# STM32F407ZGT6.net
KiCad netlist of a schematic drawn in Altium Designer
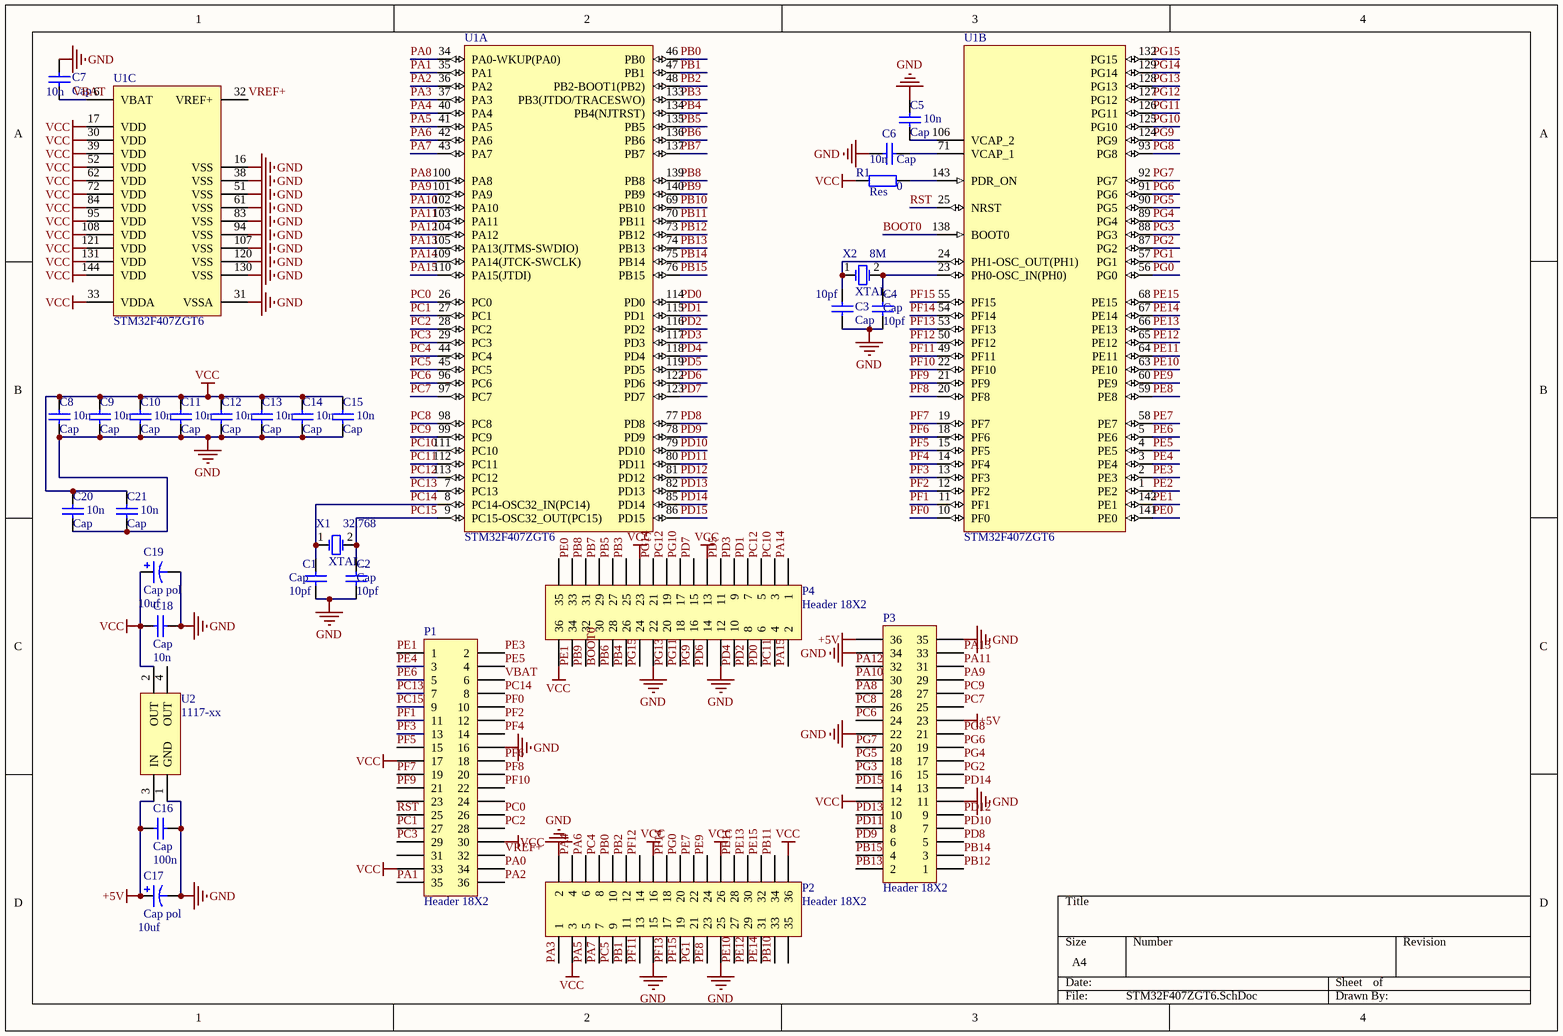
[diagram p0: STM32F407ZGT6.SchDoc]

(export (version "E")
  (design (tool "Eeschema 10.0.6"))
  (components
    (comp (ref "C1")
      (value "Cap")
      (footprint "0805C")
      (description "无极性电容")
      (fields (field (name "ALTIUM_VALUE") "10pf"))
      (libsource (lib "unsal_Devices") (part "Cap"))
    )
    (comp (ref "C2")
      (value "Cap")
      (footprint "0805C")
      (description "无极性电容")
      (fields (field (name "ALTIUM_VALUE") "10pf"))
      (libsource (lib "unsal_Devices") (part "Cap"))
    )
    (comp (ref "C3")
      (value "Cap")
      (footprint "0805C")
      (description "无极性电容")
      (fields (field (name "ALTIUM_VALUE") "10pf"))
      (libsource (lib "unsal_Devices") (part "Cap"))
    )
    (comp (ref "C4")
      (value "Cap")
      (footprint "0805C")
      (description "无极性电容")
      (fields (field (name "ALTIUM_VALUE") "10pf"))
      (libsource (lib "unsal_Devices") (part "Cap"))
    )
    (comp (ref "C5")
      (value "Cap")
      (footprint "0805C")
      (description "无极性电容")
      (fields (field (name "ALTIUM_VALUE") "10n"))
      (libsource (lib "unsal_Devices") (part "Cap"))
    )
    (comp (ref "C6")
      (value "Cap")
      (footprint "0805C")
      (description "无极性电容")
      (fields (field (name "ALTIUM_VALUE") "10n"))
      (libsource (lib "unsal_Devices") (part "Cap"))
    )
    (comp (ref "C7")
      (value "Cap")
      (footprint "0805C")
      (description "无极性电容")
      (fields (field (name "ALTIUM_VALUE") "10n"))
      (libsource (lib "unsal_Devices") (part "Cap"))
    )
    (comp (ref "C8")
      (value "Cap")
      (footprint "0805C")
      (description "无极性电容")
      (fields (field (name "ALTIUM_VALUE") "10n"))
      (libsource (lib "unsal_Devices") (part "Cap"))
    )
    (comp (ref "C9")
      (value "Cap")
      (footprint "0805C")
      (description "无极性电容")
      (fields (field (name "ALTIUM_VALUE") "10n"))
      (libsource (lib "unsal_Devices") (part "Cap"))
    )
    (comp (ref "C10")
      (value "Cap")
      (footprint "0805C")
      (description "无极性电容")
      (fields (field (name "ALTIUM_VALUE") "10n"))
      (libsource (lib "unsal_Devices") (part "Cap"))
    )
    (comp (ref "C11")
      (value "Cap")
      (footprint "0805C")
      (description "无极性电容")
      (fields (field (name "ALTIUM_VALUE") "10n"))
      (libsource (lib "unsal_Devices") (part "Cap"))
    )
    (comp (ref "C12")
      (value "Cap")
      (footprint "0805C")
      (description "无极性电容")
      (fields (field (name "ALTIUM_VALUE") "10n"))
      (libsource (lib "unsal_Devices") (part "Cap"))
    )
    (comp (ref "C13")
      (value "Cap")
      (footprint "0805C")
      (description "无极性电容")
      (fields (field (name "ALTIUM_VALUE") "10n"))
      (libsource (lib "unsal_Devices") (part "Cap"))
    )
    (comp (ref "C14")
      (value "Cap")
      (footprint "0805C")
      (description "无极性电容")
      (fields (field (name "ALTIUM_VALUE") "10n"))
      (libsource (lib "unsal_Devices") (part "Cap"))
    )
    (comp (ref "C15")
      (value "Cap")
      (footprint "0805C")
      (description "无极性电容")
      (fields (field (name "ALTIUM_VALUE") "10n"))
      (libsource (lib "unsal_Devices") (part "Cap"))
    )
    (comp (ref "C16")
      (value "Cap")
      (footprint "0805C")
      (description "无极性电容")
      (fields (field (name "ALTIUM_VALUE") "100n"))
      (libsource (lib "unsal_Devices") (part "Cap"))
    )
    (comp (ref "C17")
      (value "Cap pol")
      (footprint "CAP_SMD_3216")
      (description "极性电容")
      (fields (field (name "ALTIUM_VALUE") "10uf"))
      (libsource (lib "unsal_Devices") (part "Cap pol"))
    )
    (comp (ref "C18")
      (value "Cap")
      (footprint "0805C")
      (description "无极性电容")
      (fields (field (name "ALTIUM_VALUE") "10n"))
      (libsource (lib "unsal_Devices") (part "Cap"))
    )
    (comp (ref "C19")
      (value "Cap pol")
      (footprint "CAP_SMD_3216")
      (description "极性电容")
      (fields (field (name "ALTIUM_VALUE") "10uf"))
      (libsource (lib "unsal_Devices") (part "Cap pol"))
    )
    (comp (ref "C20")
      (value "Cap")
      (footprint "0805C")
      (description "无极性电容")
      (fields (field (name "ALTIUM_VALUE") "10n"))
      (libsource (lib "unsal_Devices") (part "Cap"))
    )
    (comp (ref "C21")
      (value "Cap")
      (footprint "0805C")
      (description "无极性电容")
      (fields (field (name "ALTIUM_VALUE") "10n"))
      (libsource (lib "unsal_Devices") (part "Cap"))
    )
    (comp (ref "P1")
      (value "Header 18X2")
      (footprint "HDR2X18")
      (description "Header, 18-Pin, Dual row")
      (fields (field (name "PUBLISHER") "Altium Limited"))
      (libsource (lib "") (part "Header 18X2_2"))
    )
    (comp (ref "P2")
      (value "Header 18X2")
      (footprint "HDR2X18")
      (description "Header, 18-Pin, Dual row")
      (fields (field (name "PUBLISHER") "Altium Limited"))
      (libsource (lib "") (part "Header 18X2_1"))
    )
    (comp (ref "P3")
      (value "Header 18X2")
      (footprint "HDR2X18")
      (description "Header, 18-Pin, Dual row")
      (fields (field (name "PUBLISHER") "Altium Limited"))
      (libsource (lib "") (part "Header 18X2_3"))
    )
    (comp (ref "P4")
      (value "Header 18X2")
      (footprint "HDR2X18")
      (description "Header, 18-Pin, Dual row")
      (fields (field (name "PUBLISHER") "Altium Limited"))
      (libsource (lib "Miscellaneous Connectors") (part "Header 18X2"))
    )
    (comp (ref "R1")
      (value "Res")
      (footprint "0805R")
      (description "电阻")
      (fields (field (name "ALTIUM_VALUE") "0"))
      (libsource (lib "unsal_Devices") (part "Res_"))
    )
    (comp (ref "U1")
      (value "STM32F407ZGT6")
      (footprint "STM-LQFP144_N")
      (fields (field (name "MANUFACTURER") "STMicroelectronics"))
      (libsource (lib "") (part "STM32F407ZGT6_1"))
    )
    (comp (ref "U2")
      (value "1117-xx")
      (footprint "SOT-223_")
      (description "稳压芯片")
      (libsource (lib "unsal_Devices") (part "1117-xx"))
    )
    (comp (ref "X1")
      (value "XTAL_")
      (footprint "XTAL_YUANZHU")
      (description "晶振")
      (fields (field (name "ALTIUM_VALUE") "32.768"))
      (libsource (lib "unsal_Devices") (part "XTAL_M"))
    )
    (comp (ref "X2")
      (value "XTAL_")
      (footprint "XTAL")
      (description "晶振")
      (fields (field (name "ALTIUM_VALUE") "8M"))
      (libsource (lib "unsal_Devices") (part "XTAL_M"))
    )
  )
  (nets
    (net (code "1") (name "+5V") (class "Default")
      (node (ref "C16") (pin "2") (pinfunction "2_2") (pintype "passive"))
      (node (ref "C17") (pin "1") (pinfunction "1_1") (pintype "passive"))
      (node (ref "P3") (pin "23") (pinfunction "23_23") (pintype "passive"))
      (node (ref "P3") (pin "36") (pinfunction "36_36") (pintype "passive"))
      (node (ref "U2") (pin "3") (pinfunction "IN_3") (pintype "passive"))
    )
    (net (code "2") (name "/BOOT0") (class "Default")
      (node (ref "P4") (pin "30") (pinfunction "30_30") (pintype "passive"))
      (node (ref "U1") (pin "138") (pinfunction "BOOT0_138") (pintype "input"))
    )
    (net (code "3") (name "/PA0") (class "Default")
      (node (ref "P1") (pin "34") (pinfunction "34_34") (pintype "passive"))
      (node (ref "U1") (pin "34") (pinfunction "PA0-WKUP(PA0)_34") (pintype "bidirectional"))
    )
    (net (code "4") (name "/PA1") (class "Default")
      (node (ref "P1") (pin "35") (pinfunction "35_35") (pintype "passive"))
      (node (ref "U1") (pin "35") (pinfunction "PA1_35") (pintype "bidirectional"))
    )
    (net (code "5") (name "/PA2") (class "Default")
      (node (ref "P1") (pin "36") (pinfunction "36_36") (pintype "passive"))
      (node (ref "U1") (pin "36") (pinfunction "PA2_36") (pintype "bidirectional"))
    )
    (net (code "6") (name "/PA3") (class "Default")
      (node (ref "P2") (pin "1") (pinfunction "1_1") (pintype "passive"))
      (node (ref "U1") (pin "37") (pinfunction "PA3_37") (pintype "bidirectional"))
    )
    (net (code "7") (name "/PA4") (class "Default")
      (node (ref "P2") (pin "4") (pinfunction "4_4") (pintype "passive"))
      (node (ref "U1") (pin "40") (pinfunction "PA4_40") (pintype "bidirectional"))
    )
    (net (code "8") (name "/PA5") (class "Default")
      (node (ref "P2") (pin "5") (pinfunction "5_5") (pintype "passive"))
      (node (ref "U1") (pin "41") (pinfunction "PA5_41") (pintype "bidirectional"))
    )
    (net (code "9") (name "/PA6") (class "Default")
      (node (ref "P2") (pin "6") (pinfunction "6_6") (pintype "passive"))
      (node (ref "U1") (pin "42") (pinfunction "PA6_42") (pintype "bidirectional"))
    )
    (net (code "10") (name "/PA7") (class "Default")
      (node (ref "P2") (pin "7") (pinfunction "7_7") (pintype "passive"))
      (node (ref "U1") (pin "43") (pinfunction "PA7_43") (pintype "bidirectional"))
    )
    (net (code "11") (name "/PA8") (class "Default")
      (node (ref "P3") (pin "28") (pinfunction "28_28") (pintype "passive"))
      (node (ref "U1") (pin "100") (pinfunction "PA8_100") (pintype "bidirectional"))
    )
    (net (code "12") (name "/PA9") (class "Default")
      (node (ref "P3") (pin "29") (pinfunction "29_29") (pintype "passive"))
      (node (ref "U1") (pin "101") (pinfunction "PA9_101") (pintype "bidirectional"))
    )
    (net (code "13") (name "/PA10") (class "Default")
      (node (ref "P3") (pin "30") (pinfunction "30_30") (pintype "passive"))
      (node (ref "U1") (pin "102") (pinfunction "PA10_102") (pintype "bidirectional"))
    )
    (net (code "14") (name "/PA11") (class "Default")
      (node (ref "P3") (pin "31") (pinfunction "31_31") (pintype "passive"))
      (node (ref "U1") (pin "103") (pinfunction "PA11_103") (pintype "bidirectional"))
    )
    (net (code "15") (name "/PA12") (class "Default")
      (node (ref "P3") (pin "32") (pinfunction "32_32") (pintype "passive"))
      (node (ref "U1") (pin "104") (pinfunction "PA12_104") (pintype "bidirectional"))
    )
    (net (code "16") (name "/PA13") (class "Default")
      (node (ref "P3") (pin "33") (pinfunction "33_33") (pintype "passive"))
      (node (ref "U1") (pin "105") (pinfunction "PA13(JTMS-SWDIO)_105") (pintype "bidirectional"))
    )
    (net (code "17") (name "/PA14") (class "Default")
      (node (ref "P4") (pin "1") (pinfunction "1_1") (pintype "passive"))
      (node (ref "U1") (pin "109") (pinfunction "PA14(JTCK-SWCLK)_109") (pintype "bidirectional"))
    )
    (net (code "18") (name "/PA15") (class "Default")
      (node (ref "P4") (pin "2") (pinfunction "2_2") (pintype "passive"))
      (node (ref "U1") (pin "110") (pinfunction "PA15(JTDI)_110") (pintype "bidirectional"))
    )
    (net (code "19") (name "/PB0") (class "Default")
      (node (ref "P2") (pin "10") (pinfunction "10_10") (pintype "passive"))
      (node (ref "U1") (pin "46") (pinfunction "PB0_46") (pintype "bidirectional"))
    )
    (net (code "20") (name "/PB1") (class "Default")
      (node (ref "P2") (pin "11") (pinfunction "11_11") (pintype "passive"))
      (node (ref "U1") (pin "47") (pinfunction "PB1_47") (pintype "bidirectional"))
    )
    (net (code "21") (name "/PB2") (class "Default")
      (node (ref "P2") (pin "12") (pinfunction "12_12") (pintype "passive"))
      (node (ref "U1") (pin "48") (pinfunction "PB2-BOOT1(PB2)_48") (pintype "bidirectional"))
    )
    (net (code "22") (name "/PB3") (class "Default")
      (node (ref "P4") (pin "25") (pinfunction "25_25") (pintype "passive"))
      (node (ref "U1") (pin "133") (pinfunction "PB3(JTDO/TRACESWO)_133") (pintype "bidirectional"))
    )
    (net (code "23") (name "/PB4") (class "Default")
      (node (ref "P4") (pin "26") (pinfunction "26_26") (pintype "passive"))
      (node (ref "U1") (pin "134") (pinfunction "PB4(NJTRST)_134") (pintype "bidirectional"))
    )
    (net (code "24") (name "/PB5") (class "Default")
      (node (ref "P4") (pin "27") (pinfunction "27_27") (pintype "passive"))
      (node (ref "U1") (pin "135") (pinfunction "PB5_135") (pintype "bidirectional"))
    )
    (net (code "25") (name "/PB6") (class "Default")
      (node (ref "P4") (pin "28") (pinfunction "28_28") (pintype "passive"))
      (node (ref "U1") (pin "136") (pinfunction "PB6_136") (pintype "bidirectional"))
    )
    (net (code "26") (name "/PB7") (class "Default")
      (node (ref "P4") (pin "29") (pinfunction "29_29") (pintype "passive"))
      (node (ref "U1") (pin "137") (pinfunction "PB7_137") (pintype "bidirectional"))
    )
    (net (code "27") (name "/PB8") (class "Default")
      (node (ref "P4") (pin "31") (pinfunction "31_31") (pintype "passive"))
      (node (ref "U1") (pin "139") (pinfunction "PB8_139") (pintype "bidirectional"))
    )
    (net (code "28") (name "/PB9") (class "Default")
      (node (ref "P4") (pin "32") (pinfunction "32_32") (pintype "passive"))
      (node (ref "U1") (pin "140") (pinfunction "PB9_140") (pintype "bidirectional"))
    )
    (net (code "29") (name "/PB10") (class "Default")
      (node (ref "P2") (pin "33") (pinfunction "33_33") (pintype "passive"))
      (node (ref "U1") (pin "69") (pinfunction "PB10_69") (pintype "bidirectional"))
    )
    (net (code "30") (name "/PB11") (class "Default")
      (node (ref "P2") (pin "34") (pinfunction "34_34") (pintype "passive"))
      (node (ref "U1") (pin "70") (pinfunction "PB11_70") (pintype "bidirectional"))
    )
    (net (code "31") (name "/PB12") (class "Default")
      (node (ref "P3") (pin "1") (pinfunction "1_1") (pintype "passive"))
      (node (ref "U1") (pin "73") (pinfunction "PB12_73") (pintype "bidirectional"))
    )
    (net (code "32") (name "/PB13") (class "Default")
      (node (ref "P3") (pin "2") (pinfunction "2_2") (pintype "passive"))
      (node (ref "U1") (pin "74") (pinfunction "PB13_74") (pintype "bidirectional"))
    )
    (net (code "33") (name "/PB14") (class "Default")
      (node (ref "P3") (pin "3") (pinfunction "3_3") (pintype "passive"))
      (node (ref "U1") (pin "75") (pinfunction "PB14_75") (pintype "bidirectional"))
    )
    (net (code "34") (name "/PB15") (class "Default")
      (node (ref "P3") (pin "4") (pinfunction "4_4") (pintype "passive"))
      (node (ref "U1") (pin "76") (pinfunction "PB15_76") (pintype "bidirectional"))
    )
    (net (code "35") (name "/PC0") (class "Default")
      (node (ref "P1") (pin "26") (pinfunction "26_26") (pintype "passive"))
      (node (ref "U1") (pin "26") (pinfunction "PC0_26") (pintype "bidirectional"))
    )
    (net (code "36") (name "/PC1") (class "Default")
      (node (ref "P1") (pin "27") (pinfunction "27_27") (pintype "passive"))
      (node (ref "U1") (pin "27") (pinfunction "PC1_27") (pintype "bidirectional"))
    )
    (net (code "37") (name "/PC2") (class "Default")
      (node (ref "P1") (pin "28") (pinfunction "28_28") (pintype "passive"))
      (node (ref "U1") (pin "28") (pinfunction "PC2_28") (pintype "bidirectional"))
    )
    (net (code "38") (name "/PC3") (class "Default")
      (node (ref "P1") (pin "29") (pinfunction "29_29") (pintype "passive"))
      (node (ref "U1") (pin "29") (pinfunction "PC3_29") (pintype "bidirectional"))
    )
    (net (code "39") (name "/PC4") (class "Default")
      (node (ref "P2") (pin "8") (pinfunction "8_8") (pintype "passive"))
      (node (ref "U1") (pin "44") (pinfunction "PC4_44") (pintype "bidirectional"))
    )
    (net (code "40") (name "/PC5") (class "Default")
      (node (ref "P2") (pin "9") (pinfunction "9_9") (pintype "passive"))
      (node (ref "U1") (pin "45") (pinfunction "PC5_45") (pintype "bidirectional"))
    )
    (net (code "41") (name "/PC6") (class "Default")
      (node (ref "P3") (pin "24") (pinfunction "24_24") (pintype "passive"))
      (node (ref "U1") (pin "96") (pinfunction "PC6_96") (pintype "bidirectional"))
    )
    (net (code "42") (name "/PC7") (class "Default")
      (node (ref "P3") (pin "25") (pinfunction "25_25") (pintype "passive"))
      (node (ref "U1") (pin "97") (pinfunction "PC7_97") (pintype "bidirectional"))
    )
    (net (code "43") (name "/PC8") (class "Default")
      (node (ref "P3") (pin "26") (pinfunction "26_26") (pintype "passive"))
      (node (ref "U1") (pin "98") (pinfunction "PC8_98") (pintype "bidirectional"))
    )
    (net (code "44") (name "/PC9") (class "Default")
      (node (ref "P3") (pin "27") (pinfunction "27_27") (pintype "passive"))
      (node (ref "U1") (pin "99") (pinfunction "PC9_99") (pintype "bidirectional"))
    )
    (net (code "45") (name "/PC10") (class "Default")
      (node (ref "P4") (pin "3") (pinfunction "3_3") (pintype "passive"))
      (node (ref "U1") (pin "111") (pinfunction "PC10_111") (pintype "bidirectional"))
    )
    (net (code "46") (name "/PC11") (class "Default")
      (node (ref "P4") (pin "4") (pinfunction "4_4") (pintype "passive"))
      (node (ref "U1") (pin "112") (pinfunction "PC11_112") (pintype "bidirectional"))
    )
    (net (code "47") (name "/PC12") (class "Default")
      (node (ref "P4") (pin "5") (pinfunction "5_5") (pintype "passive"))
      (node (ref "U1") (pin "113") (pinfunction "PC12_113") (pintype "bidirectional"))
    )
    (net (code "48") (name "/PC13") (class "Default")
      (node (ref "P1") (pin "7") (pinfunction "7_7") (pintype "passive"))
      (node (ref "U1") (pin "7") (pinfunction "PC13_7") (pintype "bidirectional"))
    )
    (net (code "49") (name "/PC14") (class "Default")
      (node (ref "C1") (pin "2") (pinfunction "2_2") (pintype "passive"))
      (node (ref "P1") (pin "8") (pinfunction "8_8") (pintype "passive"))
      (node (ref "U1") (pin "8") (pinfunction "PC14-OSC32_IN(PC14)_8") (pintype "bidirectional"))
      (node (ref "X1") (pin "1") (pinfunction "OSC1_1") (pintype "passive"))
    )
    (net (code "50") (name "/PC15") (class "Default")
      (node (ref "C2") (pin "2") (pinfunction "2_2") (pintype "passive"))
      (node (ref "P1") (pin "9") (pinfunction "9_9") (pintype "passive"))
      (node (ref "U1") (pin "9") (pinfunction "PC15-OSC32_OUT(PC15)_9") (pintype "bidirectional"))
      (node (ref "X1") (pin "2") (pinfunction "OSC2_2") (pintype "passive"))
    )
    (net (code "51") (name "/PD0") (class "Default")
      (node (ref "P4") (pin "6") (pinfunction "6_6") (pintype "passive"))
      (node (ref "U1") (pin "114") (pinfunction "PD0_114") (pintype "bidirectional"))
    )
    (net (code "52") (name "/PD1") (class "Default")
      (node (ref "P4") (pin "7") (pinfunction "7_7") (pintype "passive"))
      (node (ref "U1") (pin "115") (pinfunction "PD1_115") (pintype "bidirectional"))
    )
    (net (code "53") (name "/PD2") (class "Default")
      (node (ref "P4") (pin "8") (pinfunction "8_8") (pintype "passive"))
      (node (ref "U1") (pin "116") (pinfunction "PD2_116") (pintype "bidirectional"))
    )
    (net (code "54") (name "/PD3") (class "Default")
      (node (ref "P4") (pin "9") (pinfunction "9_9") (pintype "passive"))
      (node (ref "U1") (pin "117") (pinfunction "PD3_117") (pintype "bidirectional"))
    )
    (net (code "55") (name "/PD4") (class "Default")
      (node (ref "P4") (pin "10") (pinfunction "10_10") (pintype "passive"))
      (node (ref "U1") (pin "118") (pinfunction "PD4_118") (pintype "bidirectional"))
    )
    (net (code "56") (name "/PD5") (class "Default")
      (node (ref "P4") (pin "11") (pinfunction "11_11") (pintype "passive"))
      (node (ref "U1") (pin "119") (pinfunction "PD5_119") (pintype "bidirectional"))
    )
    (net (code "57") (name "/PD6") (class "Default")
      (node (ref "P4") (pin "14") (pinfunction "14_14") (pintype "passive"))
      (node (ref "U1") (pin "122") (pinfunction "PD6_122") (pintype "bidirectional"))
    )
    (net (code "58") (name "/PD7") (class "Default")
      (node (ref "P4") (pin "15") (pinfunction "15_15") (pintype "passive"))
      (node (ref "U1") (pin "123") (pinfunction "PD7_123") (pintype "bidirectional"))
    )
    (net (code "59") (name "/PD8") (class "Default")
      (node (ref "P3") (pin "5") (pinfunction "5_5") (pintype "passive"))
      (node (ref "U1") (pin "77") (pinfunction "PD8_77") (pintype "bidirectional"))
    )
    (net (code "60") (name "/PD9") (class "Default")
      (node (ref "P3") (pin "6") (pinfunction "6_6") (pintype "passive"))
      (node (ref "U1") (pin "78") (pinfunction "PD9_78") (pintype "bidirectional"))
    )
    (net (code "61") (name "/PD10") (class "Default")
      (node (ref "P3") (pin "7") (pinfunction "7_7") (pintype "passive"))
      (node (ref "U1") (pin "79") (pinfunction "PD10_79") (pintype "bidirectional"))
    )
    (net (code "62") (name "/PD11") (class "Default")
      (node (ref "P3") (pin "8") (pinfunction "8_8") (pintype "passive"))
      (node (ref "U1") (pin "80") (pinfunction "PD11_80") (pintype "bidirectional"))
    )
    (net (code "63") (name "/PD12") (class "Default")
      (node (ref "P3") (pin "9") (pinfunction "9_9") (pintype "passive"))
      (node (ref "U1") (pin "81") (pinfunction "PD12_81") (pintype "bidirectional"))
    )
    (net (code "64") (name "/PD13") (class "Default")
      (node (ref "P3") (pin "10") (pinfunction "10_10") (pintype "passive"))
      (node (ref "U1") (pin "82") (pinfunction "PD13_82") (pintype "bidirectional"))
    )
    (net (code "65") (name "/PD14") (class "Default")
      (node (ref "P3") (pin "13") (pinfunction "13_13") (pintype "passive"))
      (node (ref "U1") (pin "85") (pinfunction "PD14_85") (pintype "bidirectional"))
    )
    (net (code "66") (name "/PD15") (class "Default")
      (node (ref "P3") (pin "14") (pinfunction "14_14") (pintype "passive"))
      (node (ref "U1") (pin "86") (pinfunction "PD15_86") (pintype "bidirectional"))
    )
    (net (code "67") (name "/PE0") (class "Default")
      (node (ref "P4") (pin "33") (pinfunction "33_33") (pintype "passive"))
      (node (ref "U1") (pin "141") (pinfunction "PE0_141") (pintype "bidirectional"))
    )
    (net (code "68") (name "/PE1") (class "Default")
      (node (ref "P1") (pin "1") (pinfunction "1_1") (pintype "passive"))
      (node (ref "P4") (pin "34") (pinfunction "34_34") (pintype "passive"))
      (node (ref "U1") (pin "142") (pinfunction "PE1_142") (pintype "bidirectional"))
    )
    (net (code "69") (name "/PE2") (class "Default")
      (node (ref "U1") (pin "1") (pinfunction "PE2_1") (pintype "bidirectional"))
    )
    (net (code "70") (name "/PE3") (class "Default")
      (node (ref "P1") (pin "2") (pinfunction "2_2") (pintype "passive"))
      (node (ref "U1") (pin "2") (pinfunction "PE3_2") (pintype "bidirectional"))
    )
    (net (code "71") (name "/PE4") (class "Default")
      (node (ref "P1") (pin "3") (pinfunction "3_3") (pintype "passive"))
      (node (ref "U1") (pin "3") (pinfunction "PE4_3") (pintype "bidirectional"))
    )
    (net (code "72") (name "/PE5") (class "Default")
      (node (ref "P1") (pin "4") (pinfunction "4_4") (pintype "passive"))
      (node (ref "U1") (pin "4") (pinfunction "PE5_4") (pintype "bidirectional"))
    )
    (net (code "73") (name "/PE6") (class "Default")
      (node (ref "P1") (pin "5") (pinfunction "5_5") (pintype "passive"))
      (node (ref "U1") (pin "5") (pinfunction "PE6_5") (pintype "bidirectional"))
    )
    (net (code "74") (name "/PE7") (class "Default")
      (node (ref "P2") (pin "22") (pinfunction "22_22") (pintype "passive"))
      (node (ref "U1") (pin "58") (pinfunction "PE7_58") (pintype "bidirectional"))
    )
    (net (code "75") (name "/PE8") (class "Default")
      (node (ref "P2") (pin "23") (pinfunction "23_23") (pintype "passive"))
      (node (ref "U1") (pin "59") (pinfunction "PE8_59") (pintype "bidirectional"))
    )
    (net (code "76") (name "/PE9") (class "Default")
      (node (ref "P2") (pin "24") (pinfunction "24_24") (pintype "passive"))
      (node (ref "U1") (pin "60") (pinfunction "PE9_60") (pintype "bidirectional"))
    )
    (net (code "77") (name "/PE10") (class "Default")
      (node (ref "P2") (pin "27") (pinfunction "27_27") (pintype "passive"))
      (node (ref "U1") (pin "63") (pinfunction "PE10_63") (pintype "bidirectional"))
    )
    (net (code "78") (name "/PE11") (class "Default")
      (node (ref "P2") (pin "28") (pinfunction "28_28") (pintype "passive"))
      (node (ref "U1") (pin "64") (pinfunction "PE11_64") (pintype "bidirectional"))
    )
    (net (code "79") (name "/PE12") (class "Default")
      (node (ref "P2") (pin "29") (pinfunction "29_29") (pintype "passive"))
      (node (ref "U1") (pin "65") (pinfunction "PE12_65") (pintype "bidirectional"))
    )
    (net (code "80") (name "/PE13") (class "Default")
      (node (ref "P2") (pin "30") (pinfunction "30_30") (pintype "passive"))
      (node (ref "U1") (pin "66") (pinfunction "PE13_66") (pintype "bidirectional"))
    )
    (net (code "81") (name "/PE14") (class "Default")
      (node (ref "P2") (pin "31") (pinfunction "31_31") (pintype "passive"))
      (node (ref "U1") (pin "67") (pinfunction "PE14_67") (pintype "bidirectional"))
    )
    (net (code "82") (name "/PE15") (class "Default")
      (node (ref "P2") (pin "32") (pinfunction "32_32") (pintype "passive"))
      (node (ref "U1") (pin "68") (pinfunction "PE15_68") (pintype "bidirectional"))
    )
    (net (code "83") (name "/PF0") (class "Default")
      (node (ref "P1") (pin "10") (pinfunction "10_10") (pintype "passive"))
      (node (ref "U1") (pin "10") (pinfunction "PF0_10") (pintype "bidirectional"))
    )
    (net (code "84") (name "/PF1") (class "Default")
      (node (ref "P1") (pin "11") (pinfunction "11_11") (pintype "passive"))
      (node (ref "U1") (pin "11") (pinfunction "PF1_11") (pintype "bidirectional"))
    )
    (net (code "85") (name "/PF2") (class "Default")
      (node (ref "P1") (pin "12") (pinfunction "12_12") (pintype "passive"))
      (node (ref "U1") (pin "12") (pinfunction "PF2_12") (pintype "bidirectional"))
    )
    (net (code "86") (name "/PF3") (class "Default")
      (node (ref "P1") (pin "13") (pinfunction "13_13") (pintype "passive"))
      (node (ref "U1") (pin "13") (pinfunction "PF3_13") (pintype "bidirectional"))
    )
    (net (code "87") (name "/PF4") (class "Default")
      (node (ref "P1") (pin "14") (pinfunction "14_14") (pintype "passive"))
      (node (ref "U1") (pin "14") (pinfunction "PF4_14") (pintype "bidirectional"))
    )
    (net (code "88") (name "/PF5") (class "Default")
      (node (ref "P1") (pin "15") (pinfunction "15_15") (pintype "passive"))
      (node (ref "U1") (pin "15") (pinfunction "PF5_15") (pintype "bidirectional"))
    )
    (net (code "89") (name "/PF6") (class "Default")
      (node (ref "P1") (pin "18") (pinfunction "18_18") (pintype "passive"))
      (node (ref "U1") (pin "18") (pinfunction "PF6_18") (pintype "bidirectional"))
    )
    (net (code "90") (name "/PF7") (class "Default")
      (node (ref "P1") (pin "19") (pinfunction "19_19") (pintype "passive"))
      (node (ref "U1") (pin "19") (pinfunction "PF7_19") (pintype "bidirectional"))
    )
    (net (code "91") (name "/PF8") (class "Default")
      (node (ref "P1") (pin "20") (pinfunction "20_20") (pintype "passive"))
      (node (ref "U1") (pin "20") (pinfunction "PF8_20") (pintype "bidirectional"))
    )
    (net (code "92") (name "/PF9") (class "Default")
      (node (ref "P1") (pin "21") (pinfunction "21_21") (pintype "passive"))
      (node (ref "U1") (pin "21") (pinfunction "PF9_21") (pintype "bidirectional"))
    )
    (net (code "93") (name "/PF10") (class "Default")
      (node (ref "P1") (pin "22") (pinfunction "22_22") (pintype "passive"))
      (node (ref "U1") (pin "22") (pinfunction "PF10_22") (pintype "bidirectional"))
    )
    (net (code "94") (name "/PF11") (class "Default")
      (node (ref "P2") (pin "13") (pinfunction "13_13") (pintype "passive"))
      (node (ref "U1") (pin "49") (pinfunction "PF11_49") (pintype "bidirectional"))
    )
    (net (code "95") (name "/PF12") (class "Default")
      (node (ref "P2") (pin "14") (pinfunction "14_14") (pintype "passive"))
      (node (ref "U1") (pin "50") (pinfunction "PF12_50") (pintype "bidirectional"))
    )
    (net (code "96") (name "/PF13") (class "Default")
      (node (ref "P2") (pin "17") (pinfunction "17_17") (pintype "passive"))
      (node (ref "U1") (pin "53") (pinfunction "PF13_53") (pintype "bidirectional"))
    )
    (net (code "97") (name "/PF14") (class "Default")
      (node (ref "P2") (pin "18") (pinfunction "18_18") (pintype "passive"))
      (node (ref "U1") (pin "54") (pinfunction "PF14_54") (pintype "bidirectional"))
    )
    (net (code "98") (name "/PF15") (class "Default")
      (node (ref "P2") (pin "19") (pinfunction "19_19") (pintype "passive"))
      (node (ref "U1") (pin "55") (pinfunction "PF15_55") (pintype "bidirectional"))
    )
    (net (code "99") (name "/PG0") (class "Default")
      (node (ref "P2") (pin "20") (pinfunction "20_20") (pintype "passive"))
      (node (ref "U1") (pin "56") (pinfunction "PG0_56") (pintype "bidirectional"))
    )
    (net (code "100") (name "/PG1") (class "Default")
      (node (ref "P2") (pin "21") (pinfunction "21_21") (pintype "passive"))
      (node (ref "U1") (pin "57") (pinfunction "PG1_57") (pintype "bidirectional"))
    )
    (net (code "101") (name "/PG2") (class "Default")
      (node (ref "P3") (pin "15") (pinfunction "15_15") (pintype "passive"))
      (node (ref "U1") (pin "87") (pinfunction "PG2_87") (pintype "bidirectional"))
    )
    (net (code "102") (name "/PG3") (class "Default")
      (node (ref "P3") (pin "16") (pinfunction "16_16") (pintype "passive"))
      (node (ref "U1") (pin "88") (pinfunction "PG3_88") (pintype "bidirectional"))
    )
    (net (code "103") (name "/PG4") (class "Default")
      (node (ref "P3") (pin "17") (pinfunction "17_17") (pintype "passive"))
      (node (ref "U1") (pin "89") (pinfunction "PG4_89") (pintype "bidirectional"))
    )
    (net (code "104") (name "/PG5") (class "Default")
      (node (ref "P3") (pin "18") (pinfunction "18_18") (pintype "passive"))
      (node (ref "U1") (pin "90") (pinfunction "PG5_90") (pintype "bidirectional"))
    )
    (net (code "105") (name "/PG6") (class "Default")
      (node (ref "P3") (pin "19") (pinfunction "19_19") (pintype "passive"))
      (node (ref "U1") (pin "91") (pinfunction "PG6_91") (pintype "bidirectional"))
    )
    (net (code "106") (name "/PG7") (class "Default")
      (node (ref "P3") (pin "20") (pinfunction "20_20") (pintype "passive"))
      (node (ref "U1") (pin "92") (pinfunction "PG7_92") (pintype "bidirectional"))
    )
    (net (code "107") (name "/PG8") (class "Default")
      (node (ref "P3") (pin "21") (pinfunction "21_21") (pintype "passive"))
      (node (ref "U1") (pin "93") (pinfunction "PG8_93") (pintype "bidirectional"))
    )
    (net (code "108") (name "/PG9") (class "Default")
      (node (ref "P4") (pin "16") (pinfunction "16_16") (pintype "passive"))
      (node (ref "U1") (pin "124") (pinfunction "PG9_124") (pintype "bidirectional"))
    )
    (net (code "109") (name "/PG10") (class "Default")
      (node (ref "P4") (pin "17") (pinfunction "17_17") (pintype "passive"))
      (node (ref "U1") (pin "125") (pinfunction "PG10_125") (pintype "bidirectional"))
    )
    (net (code "110") (name "/PG11") (class "Default")
      (node (ref "P4") (pin "18") (pinfunction "18_18") (pintype "passive"))
      (node (ref "U1") (pin "126") (pinfunction "PG11_126") (pintype "bidirectional"))
    )
    (net (code "111") (name "/PG12") (class "Default")
      (node (ref "P4") (pin "19") (pinfunction "19_19") (pintype "passive"))
      (node (ref "U1") (pin "127") (pinfunction "PG12_127") (pintype "bidirectional"))
    )
    (net (code "112") (name "/PG13") (class "Default")
      (node (ref "P4") (pin "20") (pinfunction "20_20") (pintype "passive"))
      (node (ref "U1") (pin "128") (pinfunction "PG13_128") (pintype "bidirectional"))
    )
    (net (code "113") (name "/PG14") (class "Default")
      (node (ref "P4") (pin "21") (pinfunction "21_21") (pintype "passive"))
      (node (ref "U1") (pin "129") (pinfunction "PG14_129") (pintype "bidirectional"))
    )
    (net (code "114") (name "/PG15") (class "Default")
      (node (ref "P4") (pin "24") (pinfunction "24_24") (pintype "passive"))
      (node (ref "U1") (pin "132") (pinfunction "PG15_132") (pintype "bidirectional"))
    )
    (net (code "115") (name "/RST") (class "Default")
      (node (ref "P1") (pin "25") (pinfunction "25_25") (pintype "passive"))
      (node (ref "U1") (pin "25") (pinfunction "NRST_25") (pintype "bidirectional"))
    )
    (net (code "116") (name "/VBAT") (class "Default")
      (node (ref "C7") (pin "2") (pinfunction "2_2") (pintype "passive"))
      (node (ref "P1") (pin "6") (pinfunction "6_6") (pintype "passive"))
      (node (ref "U1") (pin "6") (pinfunction "VBAT_6") (pintype "power_in"))
    )
    (net (code "117") (name "/VREF+") (class "Default")
      (node (ref "P1") (pin "32") (pinfunction "32_32") (pintype "passive"))
      (node (ref "U1") (pin "32") (pinfunction "VREF+_32") (pintype "power_in"))
    )
    (net (code "118") (name "GND") (class "Default")
      (node (ref "C1") (pin "1") (pinfunction "1_1") (pintype "passive"))
      (node (ref "C10") (pin "1") (pinfunction "1_1") (pintype "passive"))
      (node (ref "C11") (pin "1") (pinfunction "1_1") (pintype "passive"))
      (node (ref "C12") (pin "1") (pinfunction "1_1") (pintype "passive"))
      (node (ref "C13") (pin "1") (pinfunction "1_1") (pintype "passive"))
      (node (ref "C14") (pin "1") (pinfunction "1_1") (pintype "passive"))
      (node (ref "C15") (pin "1") (pinfunction "1_1") (pintype "passive"))
      (node (ref "C16") (pin "1") (pinfunction "1_1") (pintype "passive"))
      (node (ref "C17") (pin "2") (pinfunction "2_2") (pintype "passive"))
      (node (ref "C18") (pin "1") (pinfunction "1_1") (pintype "passive"))
      (node (ref "C19") (pin "2") (pinfunction "2_2") (pintype "passive"))
      (node (ref "C2") (pin "1") (pinfunction "1_1") (pintype "passive"))
      (node (ref "C20") (pin "1") (pinfunction "1_1") (pintype "passive"))
      (node (ref "C21") (pin "1") (pinfunction "1_1") (pintype "passive"))
      (node (ref "C3") (pin "1") (pinfunction "1_1") (pintype "passive"))
      (node (ref "C4") (pin "1") (pinfunction "1_1") (pintype "passive"))
      (node (ref "C5") (pin "2") (pinfunction "2_2") (pintype "passive"))
      (node (ref "C6") (pin "1") (pinfunction "1_1") (pintype "passive"))
      (node (ref "C7") (pin "1") (pinfunction "1_1") (pintype "passive"))
      (node (ref "C8") (pin "1") (pinfunction "1_1") (pintype "passive"))
      (node (ref "C9") (pin "1") (pinfunction "1_1") (pintype "passive"))
      (node (ref "P1") (pin "16") (pinfunction "16_16") (pintype "passive"))
      (node (ref "P2") (pin "15") (pinfunction "15_15") (pintype "passive"))
      (node (ref "P2") (pin "2") (pinfunction "2_2") (pintype "passive"))
      (node (ref "P2") (pin "25") (pinfunction "25_25") (pintype "passive"))
      (node (ref "P3") (pin "11") (pinfunction "11_11") (pintype "passive"))
      (node (ref "P3") (pin "22") (pinfunction "22_22") (pintype "passive"))
      (node (ref "P3") (pin "34") (pinfunction "34_34") (pintype "passive"))
      (node (ref "P3") (pin "35") (pinfunction "35_35") (pintype "passive"))
      (node (ref "P4") (pin "12") (pinfunction "12_12") (pintype "passive"))
      (node (ref "P4") (pin "22") (pinfunction "22_22") (pintype "passive"))
      (node (ref "U1") (pin "107") (pinfunction "VSS_107") (pintype "power_in"))
      (node (ref "U1") (pin "120") (pinfunction "VSS_120") (pintype "power_in"))
      (node (ref "U1") (pin "130") (pinfunction "VSS_130") (pintype "power_in"))
      (node (ref "U1") (pin "16") (pinfunction "VSS_16") (pintype "power_in"))
      (node (ref "U1") (pin "31") (pinfunction "VSSA_31") (pintype "power_in"))
      (node (ref "U1") (pin "38") (pinfunction "VSS_38") (pintype "power_in"))
      (node (ref "U1") (pin "51") (pinfunction "VSS_51") (pintype "power_in"))
      (node (ref "U1") (pin "61") (pinfunction "VSS_61") (pintype "power_in"))
      (node (ref "U1") (pin "83") (pinfunction "VSS_83") (pintype "power_in"))
      (node (ref "U1") (pin "94") (pinfunction "VSS_94") (pintype "power_in"))
      (node (ref "U2") (pin "1") (pinfunction "GND_1") (pintype "passive"))
    )
    (net (code "119") (name "Net-(U1B-PDR_ON)") (class "Default")
      (node (ref "R1") (pin "2") (pinfunction "2_2") (pintype "passive"))
      (node (ref "U1") (pin "143") (pinfunction "PDR_ON_143") (pintype "input"))
    )
    (net (code "120") (name "Net-(U1B-PH0-OSC_IN(PH0))") (class "Default")
      (node (ref "C4") (pin "2") (pinfunction "2_2") (pintype "passive"))
      (node (ref "U1") (pin "23") (pinfunction "PH0-OSC_IN(PH0)_23") (pintype "bidirectional"))
      (node (ref "X2") (pin "2") (pinfunction "OSC2_2") (pintype "passive"))
    )
    (net (code "121") (name "Net-(U1B-PH1-OSC_OUT(PH1))") (class "Default")
      (node (ref "C3") (pin "2") (pinfunction "2_2") (pintype "passive"))
      (node (ref "U1") (pin "24") (pinfunction "PH1-OSC_OUT(PH1)_24") (pintype "bidirectional"))
      (node (ref "X2") (pin "1") (pinfunction "OSC1_1") (pintype "passive"))
    )
    (net (code "122") (name "Net-(U1B-VCAP_1)") (class "Default")
      (node (ref "C6") (pin "2") (pinfunction "2_2") (pintype "passive"))
      (node (ref "U1") (pin "71") (pinfunction "VCAP_1_71") (pintype "power_in"))
    )
    (net (code "123") (name "Net-(U1B-VCAP_2)") (class "Default")
      (node (ref "C5") (pin "1") (pinfunction "1_1") (pintype "passive"))
      (node (ref "U1") (pin "106") (pinfunction "VCAP_2_106") (pintype "power_in"))
    )
    (net (code "124") (name "VCC") (class "Default")
      (node (ref "C10") (pin "2") (pinfunction "2_2") (pintype "passive"))
      (node (ref "C11") (pin "2") (pinfunction "2_2") (pintype "passive"))
      (node (ref "C12") (pin "2") (pinfunction "2_2") (pintype "passive"))
      (node (ref "C13") (pin "2") (pinfunction "2_2") (pintype "passive"))
      (node (ref "C14") (pin "2") (pinfunction "2_2") (pintype "passive"))
      (node (ref "C15") (pin "2") (pinfunction "2_2") (pintype "passive"))
      (node (ref "C18") (pin "2") (pinfunction "2_2") (pintype "passive"))
      (node (ref "C19") (pin "1") (pinfunction "1_1") (pintype "passive"))
      (node (ref "C20") (pin "2") (pinfunction "2_2") (pintype "passive"))
      (node (ref "C21") (pin "2") (pinfunction "2_2") (pintype "passive"))
      (node (ref "C8") (pin "2") (pinfunction "2_2") (pintype "passive"))
      (node (ref "C9") (pin "2") (pinfunction "2_2") (pintype "passive"))
      (node (ref "P1") (pin "17") (pinfunction "17_17") (pintype "passive"))
      (node (ref "P1") (pin "30") (pinfunction "30_30") (pintype "passive"))
      (node (ref "P1") (pin "33") (pinfunction "33_33") (pintype "passive"))
      (node (ref "P2") (pin "16") (pinfunction "16_16") (pintype "passive"))
      (node (ref "P2") (pin "26") (pinfunction "26_26") (pintype "passive"))
      (node (ref "P2") (pin "3") (pinfunction "3_3") (pintype "passive"))
      (node (ref "P2") (pin "36") (pinfunction "36_36") (pintype "passive"))
      (node (ref "P3") (pin "12") (pinfunction "12_12") (pintype "passive"))
      (node (ref "P4") (pin "13") (pinfunction "13_13") (pintype "passive"))
      (node (ref "P4") (pin "23") (pinfunction "23_23") (pintype "passive"))
      (node (ref "P4") (pin "36") (pinfunction "36_36") (pintype "passive"))
      (node (ref "R1") (pin "1") (pinfunction "1_1") (pintype "passive"))
      (node (ref "U1") (pin "108") (pinfunction "VDD_108") (pintype "power_in"))
      (node (ref "U1") (pin "121") (pinfunction "VDD_121") (pintype "power_in"))
      (node (ref "U1") (pin "131") (pinfunction "VDD_131") (pintype "power_in"))
      (node (ref "U1") (pin "144") (pinfunction "VDD_144") (pintype "power_in"))
      (node (ref "U1") (pin "17") (pinfunction "VDD_17") (pintype "power_in"))
      (node (ref "U1") (pin "30") (pinfunction "VDD_30") (pintype "power_in"))
      (node (ref "U1") (pin "33") (pinfunction "VDDA_33") (pintype "power_in"))
      (node (ref "U1") (pin "39") (pinfunction "VDD_39") (pintype "power_in"))
      (node (ref "U1") (pin "52") (pinfunction "VDD_52") (pintype "power_in"))
      (node (ref "U1") (pin "62") (pinfunction "VDD_62") (pintype "power_in"))
      (node (ref "U1") (pin "72") (pinfunction "VDD_72") (pintype "power_in"))
      (node (ref "U1") (pin "84") (pinfunction "VDD_84") (pintype "power_in"))
      (node (ref "U1") (pin "95") (pinfunction "VDD_95") (pintype "power_in"))
      (node (ref "U2") (pin "2") (pinfunction "OUT_2") (pintype "passive"))
    )
    (net (code "125") (name "unconnected-(P1-Pad23)") (class "Default")
      (node (ref "P1") (pin "23") (pinfunction "23_23") (pintype "passive"))
    )
    (net (code "126") (name "unconnected-(P1-Pad24)") (class "Default")
      (node (ref "P1") (pin "24") (pinfunction "24_24") (pintype "passive"))
    )
    (net (code "127") (name "unconnected-(P1-Pad31)") (class "Default")
      (node (ref "P1") (pin "31") (pinfunction "31_31") (pintype "passive"))
    )
    (net (code "128") (name "unconnected-(P2-Pad35)") (class "Default")
      (node (ref "P2") (pin "35") (pinfunction "35_35") (pintype "passive"))
    )
    (net (code "129") (name "unconnected-(P4-Pad35)") (class "Default")
      (node (ref "P4") (pin "35") (pinfunction "35_35") (pintype "passive"))
    )
    (net (code "130") (name "unconnected-(U2-OUT-Pad4)") (class "Default")
      (node (ref "U2") (pin "4") (pinfunction "OUT_4") (pintype "passive"))
    )
  )
)
